# 09_RGB_LCD.net
KiCad netlist of a schematic drawn in Altium Designer
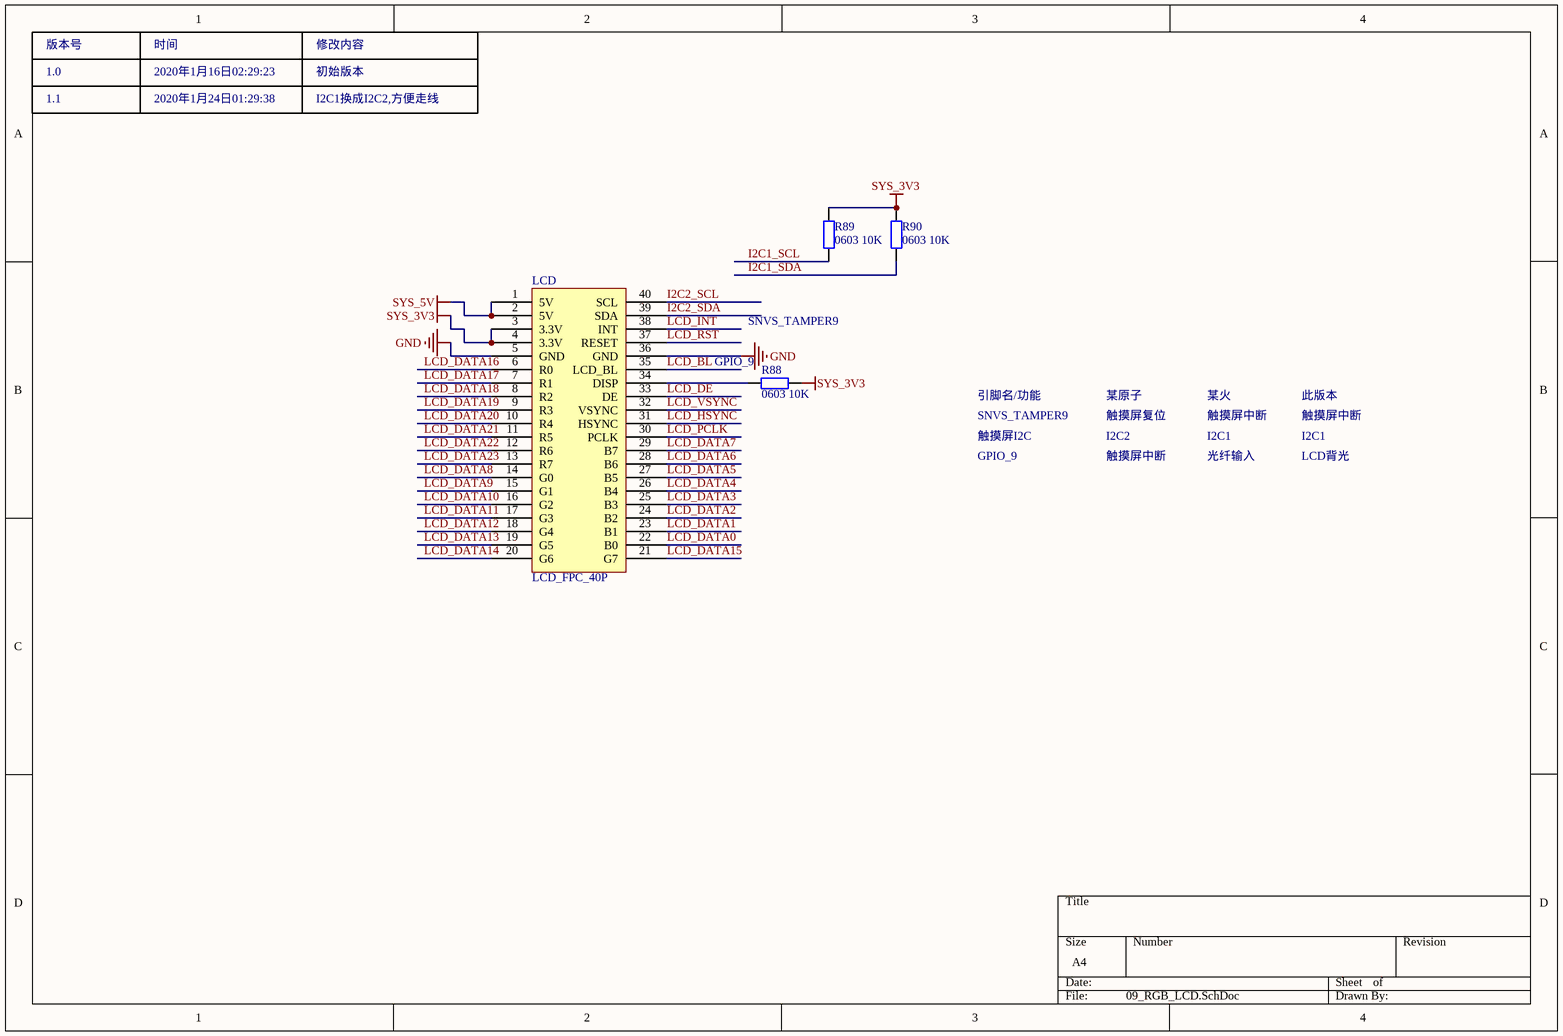
[diagram p0: 09_RGB_LCD.SchDoc]

(export (version "E")
  (design (tool "Eeschema 10.0.6"))
  (components
    (comp (ref "LCD")
      (value "LCD_FPC_40P")
      (footprint "FPC40P_P")
      (libsource (lib "Integrated_Library2") (part "LCD_FPC_40P"))
    )
    (comp (ref "R88")
      (value "0603 10K")
      (footprint "LC-0603_R")
      (description "贴片电阻")
      (libsource (lib "JLC") (part "0603 1.1KΩ (1101) 1%"))
    )
    (comp (ref "R89")
      (value "0603 10K")
      (footprint "LC-0603_R")
      (description "贴片电阻")
      (libsource (lib "") (part "0603 1.1KΩ (1101) 1%_1"))
    )
    (comp (ref "R90")
      (value "0603 10K")
      (footprint "LC-0603_R")
      (description "贴片电阻")
      (libsource (lib "") (part "0603 1.1KΩ (1101) 1%_1"))
    )
  )
  (nets
    (net (code "1") (name "/I2C1_SCL") (class "Default")
      (node (ref "R89") (pin "1") (pinfunction "1_1") (pintype "passive"))
    )
    (net (code "2") (name "/I2C1_SDA") (class "Default")
      (node (ref "R90") (pin "1") (pinfunction "1_1") (pintype "passive"))
    )
    (net (code "3") (name "/I2C2_SCL") (class "Default")
      (node (ref "LCD") (pin "40") (pinfunction "SCL_40") (pintype "passive"))
    )
    (net (code "4") (name "/I2C2_SDA") (class "Default")
      (node (ref "LCD") (pin "39") (pinfunction "SDA_39") (pintype "passive"))
    )
    (net (code "5") (name "/LCD_BL") (class "Default")
      (node (ref "LCD") (pin "35") (pinfunction "LCD_BL_35") (pintype "passive"))
    )
    (net (code "6") (name "/LCD_DATA0") (class "Default")
      (node (ref "LCD") (pin "22") (pinfunction "B0_22") (pintype "passive"))
    )
    (net (code "7") (name "/LCD_DATA1") (class "Default")
      (node (ref "LCD") (pin "23") (pinfunction "B1_23") (pintype "passive"))
    )
    (net (code "8") (name "/LCD_DATA2") (class "Default")
      (node (ref "LCD") (pin "24") (pinfunction "B2_24") (pintype "passive"))
    )
    (net (code "9") (name "/LCD_DATA3") (class "Default")
      (node (ref "LCD") (pin "25") (pinfunction "B3_25") (pintype "passive"))
    )
    (net (code "10") (name "/LCD_DATA4") (class "Default")
      (node (ref "LCD") (pin "26") (pinfunction "B4_26") (pintype "passive"))
    )
    (net (code "11") (name "/LCD_DATA5") (class "Default")
      (node (ref "LCD") (pin "27") (pinfunction "B5_27") (pintype "passive"))
    )
    (net (code "12") (name "/LCD_DATA6") (class "Default")
      (node (ref "LCD") (pin "28") (pinfunction "B6_28") (pintype "passive"))
    )
    (net (code "13") (name "/LCD_DATA7") (class "Default")
      (node (ref "LCD") (pin "29") (pinfunction "B7_29") (pintype "passive"))
    )
    (net (code "14") (name "/LCD_DATA8") (class "Default")
      (node (ref "LCD") (pin "14") (pinfunction "G0_14") (pintype "passive"))
    )
    (net (code "15") (name "/LCD_DATA9") (class "Default")
      (node (ref "LCD") (pin "15") (pinfunction "G1_15") (pintype "passive"))
    )
    (net (code "16") (name "/LCD_DATA10") (class "Default")
      (node (ref "LCD") (pin "16") (pinfunction "G2_16") (pintype "passive"))
    )
    (net (code "17") (name "/LCD_DATA11") (class "Default")
      (node (ref "LCD") (pin "17") (pinfunction "G3_17") (pintype "passive"))
    )
    (net (code "18") (name "/LCD_DATA12") (class "Default")
      (node (ref "LCD") (pin "18") (pinfunction "G4_18") (pintype "passive"))
    )
    (net (code "19") (name "/LCD_DATA13") (class "Default")
      (node (ref "LCD") (pin "19") (pinfunction "G5_19") (pintype "passive"))
    )
    (net (code "20") (name "/LCD_DATA14") (class "Default")
      (node (ref "LCD") (pin "20") (pinfunction "G6_20") (pintype "passive"))
    )
    (net (code "21") (name "/LCD_DATA15") (class "Default")
      (node (ref "LCD") (pin "21") (pinfunction "G7_21") (pintype "passive"))
    )
    (net (code "22") (name "/LCD_DATA16") (class "Default")
      (node (ref "LCD") (pin "6") (pinfunction "R0_6") (pintype "passive"))
    )
    (net (code "23") (name "/LCD_DATA17") (class "Default")
      (node (ref "LCD") (pin "7") (pinfunction "R1_7") (pintype "passive"))
    )
    (net (code "24") (name "/LCD_DATA18") (class "Default")
      (node (ref "LCD") (pin "8") (pinfunction "R2_8") (pintype "passive"))
    )
    (net (code "25") (name "/LCD_DATA19") (class "Default")
      (node (ref "LCD") (pin "9") (pinfunction "R3_9") (pintype "passive"))
    )
    (net (code "26") (name "/LCD_DATA20") (class "Default")
      (node (ref "LCD") (pin "10") (pinfunction "R4_10") (pintype "passive"))
    )
    (net (code "27") (name "/LCD_DATA21") (class "Default")
      (node (ref "LCD") (pin "11") (pinfunction "R5_11") (pintype "passive"))
    )
    (net (code "28") (name "/LCD_DATA22") (class "Default")
      (node (ref "LCD") (pin "12") (pinfunction "R6_12") (pintype "passive"))
    )
    (net (code "29") (name "/LCD_DATA23") (class "Default")
      (node (ref "LCD") (pin "13") (pinfunction "R7_13") (pintype "passive"))
    )
    (net (code "30") (name "/LCD_DE") (class "Default")
      (node (ref "LCD") (pin "33") (pinfunction "DE_33") (pintype "passive"))
    )
    (net (code "31") (name "/LCD_HSYNC") (class "Default")
      (node (ref "LCD") (pin "31") (pinfunction "HSYNC_31") (pintype "passive"))
    )
    (net (code "32") (name "/LCD_INT") (class "Default")
      (node (ref "LCD") (pin "38") (pinfunction "INT_38") (pintype "passive"))
    )
    (net (code "33") (name "/LCD_PCLK") (class "Default")
      (node (ref "LCD") (pin "30") (pinfunction "PCLK_30") (pintype "passive"))
    )
    (net (code "34") (name "/LCD_RST") (class "Default")
      (node (ref "LCD") (pin "37") (pinfunction "RESET_37") (pintype "passive"))
    )
    (net (code "35") (name "/LCD_VSYNC") (class "Default")
      (node (ref "LCD") (pin "32") (pinfunction "VSYNC_32") (pintype "passive"))
    )
    (net (code "36") (name "GND") (class "Default")
      (node (ref "LCD") (pin "36") (pinfunction "GND_36") (pintype "passive"))
      (node (ref "LCD") (pin "5") (pinfunction "GND_5") (pintype "passive"))
    )
    (net (code "37") (name "Net-(LCD-DISP)") (class "Default")
      (node (ref "LCD") (pin "34") (pinfunction "DISP_34") (pintype "passive"))
      (node (ref "R88") (pin "1") (pinfunction "1_1") (pintype "passive"))
    )
    (net (code "38") (name "SYS_3V3") (class "Default")
      (node (ref "LCD") (pin "3") (pinfunction "3.3V_3") (pintype "passive"))
      (node (ref "LCD") (pin "4") (pinfunction "3.3V_4") (pintype "passive"))
      (node (ref "R88") (pin "2") (pinfunction "2_2") (pintype "passive"))
      (node (ref "R89") (pin "2") (pinfunction "2_2") (pintype "passive"))
      (node (ref "R90") (pin "2") (pinfunction "2_2") (pintype "passive"))
    )
    (net (code "39") (name "SYS_5V") (class "Default")
      (node (ref "LCD") (pin "1") (pinfunction "5V_1") (pintype "passive"))
      (node (ref "LCD") (pin "2") (pinfunction "5V_2") (pintype "passive"))
    )
  )
)
